# CC2530-CP2102-USB-V02-006.net
KiCad netlist of a schematic drawn in EAGLE
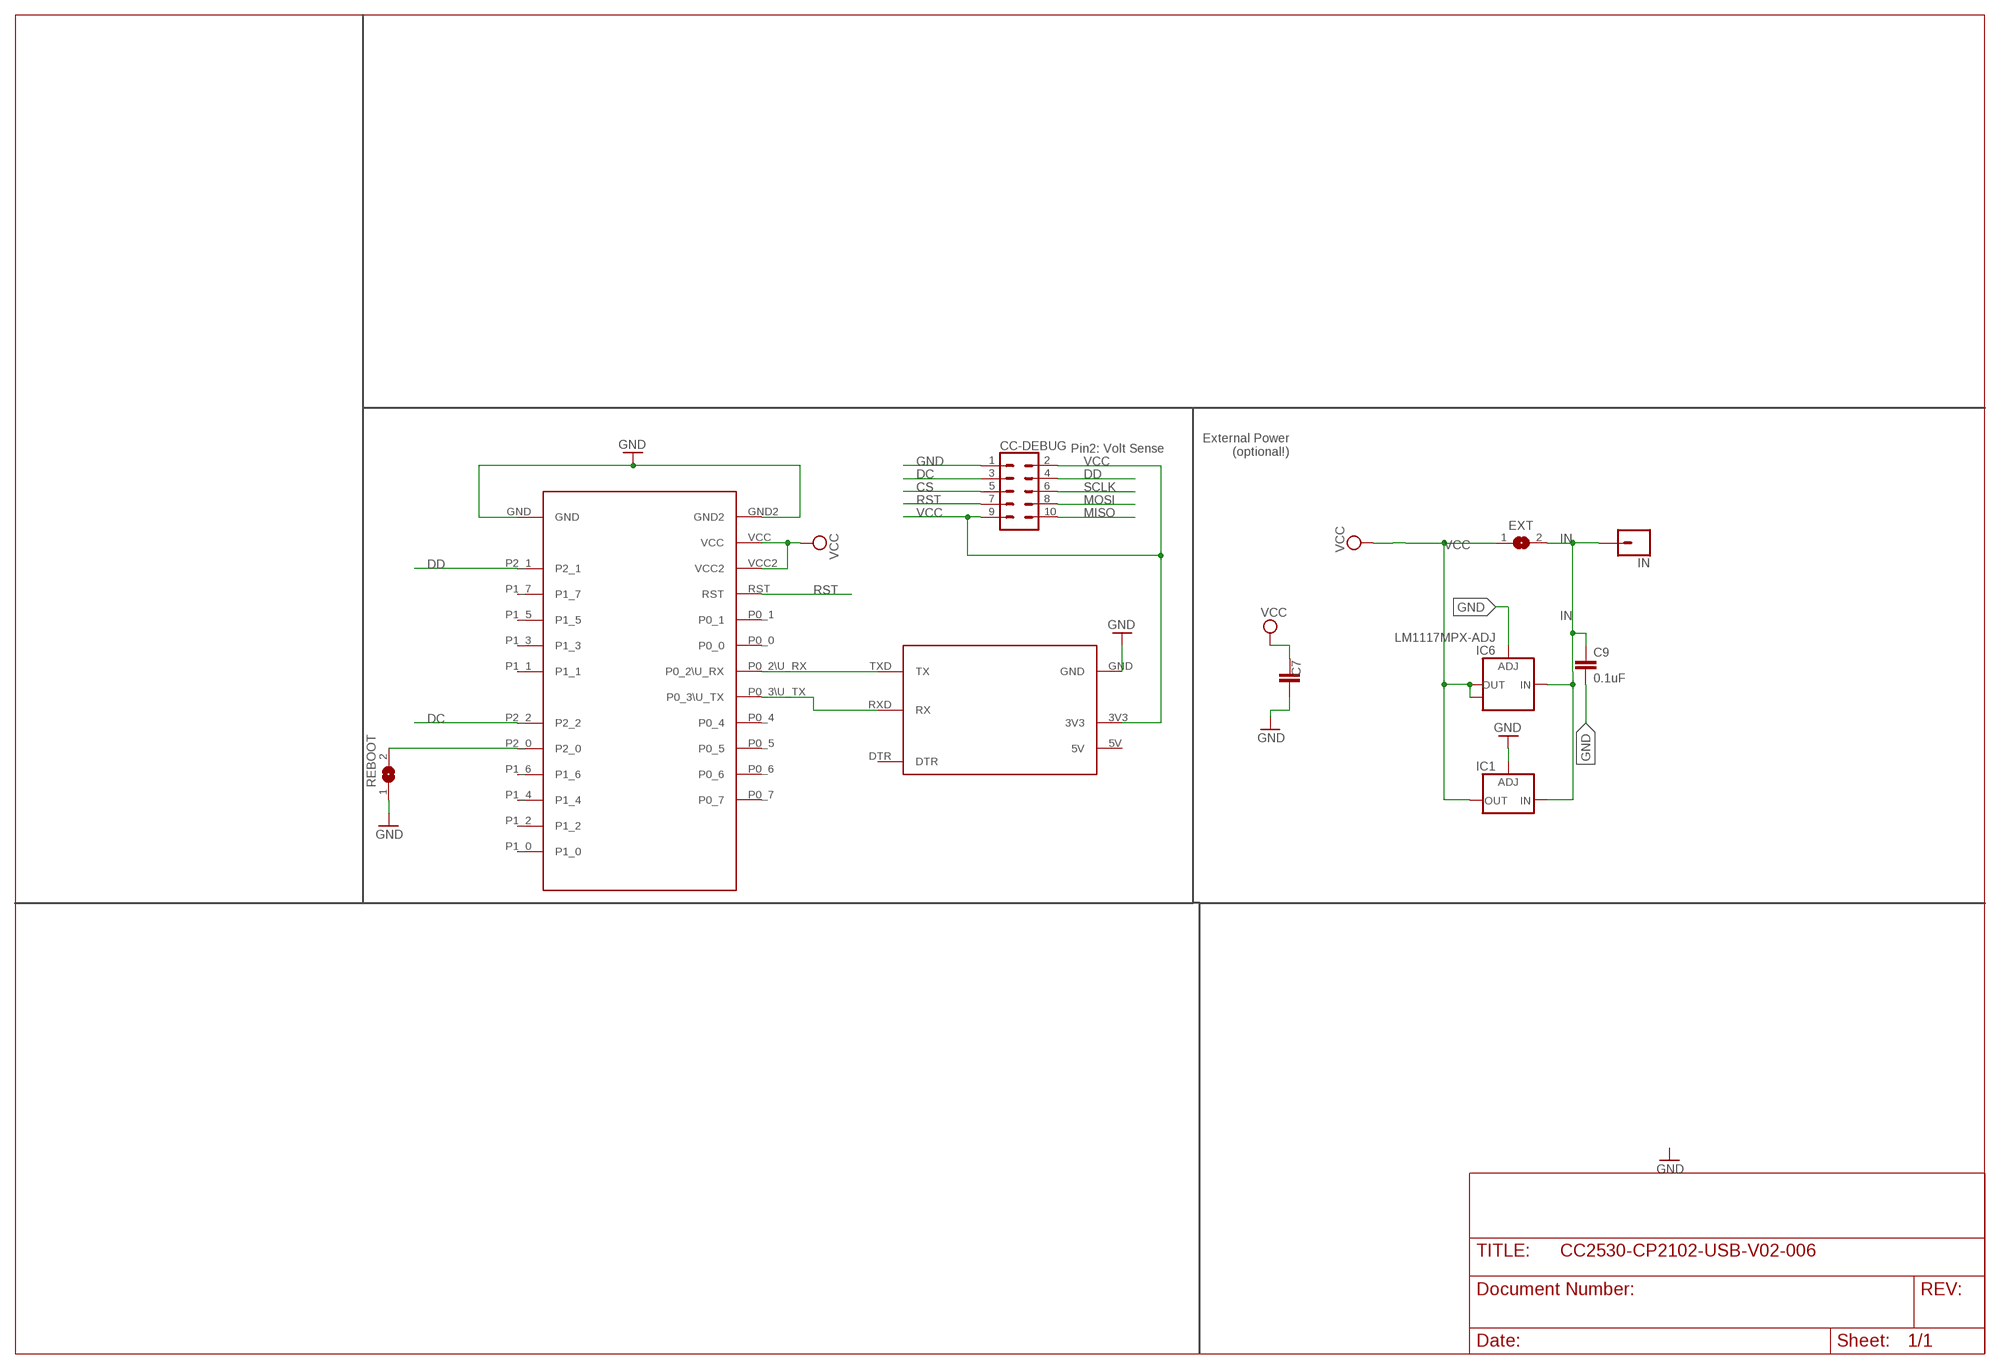
[diagram p0: schematic, sheet 1]

(export (version "E")
  (design (tool "Eeschema 10.0.6"))
  (components
    (comp (ref "C7")
      (value "C-EUC1812")
      (footprint "eagle-import:C1812")
      (libsource (lib "eagle-import") (part "C-EUC1812"))
    )
    (comp (ref "C9")
      (value "0.1uF")
      (footprint "eagle-import:C1206")
      (libsource (lib "eagle-import") (part "C-EUC1206"))
    )
    (comp (ref "CC-DEBUG")
      (value "CONN_05X2SHD_LOCK")
      (footprint "eagle-import:2X5-SHROUDED_LOCK")
      (libsource (lib "eagle-import") (part "CONN_05X2SHD_LOCK"))
    )
    (comp (ref "EXT") (value "SJ") (footprint "eagle-import:SJ") (libsource (lib "eagle-import") (part "SJ")))
    (comp (ref "IC1")
      (value "LD117ADT50TR")
      (footprint "eagle-import:DPACK")
      (libsource (lib "eagle-import") (part "LD117A?DT50TR"))
    )
    (comp (ref "IC6")
      (value "LM1117MPX-ADJ")
      (footprint "eagle-import:SOT223")
      (libsource (lib "eagle-import") (part "LM1117MPX-ADJ"))
    )
    (comp (ref "IN")
      (value "CONN_01")
      (footprint "eagle-import:1X01")
      (libsource (lib "eagle-import") (part "CONN_01"))
    )
    (comp (ref "REBOOT")
      (value "SJ")
      (footprint "eagle-import:SJ")
      (libsource (lib "eagle-import") (part "SJ"))
    )
    (comp (ref "U$1")
      (value "CP2101")
      (footprint "eagle-import:CP2101-BEAKOUT")
      (libsource (lib "eagle-import") (part "CP2101"))
    )
    (comp (ref "U$3")
      (value "CC2530_MODULE")
      (footprint "eagle-import:CC2530_DIL")
      (libsource (lib "eagle-import") (part "CC2530_MODULE"))
    )
  )
  (nets
    (net (code "1") (name "/5V") (class "Default")
      (node (ref "U$1") (pin "5V") (pinfunction "5V_5V") (pintype "power_in"))
    )
    (net (code "2") (name "/CS") (class "Default")
      (node (ref "CC-DEBUG") (pin "5") (pinfunction "5_5") (pintype "passive"))
    )
    (net (code "3") (name "/DC") (class "Default")
      (node (ref "CC-DEBUG") (pin "3") (pinfunction "3_3") (pintype "passive"))
      (node (ref "U$3") (pin "P2_2") (pinfunction "P2_2_P2_2") (pintype "bidirectional"))
    )
    (net (code "4") (name "/DD") (class "Default")
      (node (ref "CC-DEBUG") (pin "4") (pinfunction "4_4") (pintype "passive"))
      (node (ref "U$3") (pin "P2_1") (pinfunction "P2_1_P2_1") (pintype "bidirectional"))
    )
    (net (code "5") (name "/IN") (class "Default")
      (node (ref "C9") (pin "1") (pinfunction "1_1") (pintype "passive"))
      (node (ref "EXT") (pin "2") (pinfunction "2_2") (pintype "passive"))
      (node (ref "IC1") (pin "3") (pinfunction "IN_3") (pintype "input"))
      (node (ref "IC6") (pin "3") (pinfunction "IN_3") (pintype "input"))
      (node (ref "IN") (pin "1") (pinfunction "1_1") (pintype "passive"))
    )
    (net (code "6") (name "/MISO") (class "Default")
      (node (ref "CC-DEBUG") (pin "10") (pinfunction "10_10") (pintype "passive"))
    )
    (net (code "7") (name "/MOSI") (class "Default")
      (node (ref "CC-DEBUG") (pin "8") (pinfunction "8_8") (pintype "passive"))
    )
    (net (code "8") (name "/RST") (class "Default")
      (node (ref "CC-DEBUG") (pin "7") (pinfunction "7_7") (pintype "passive"))
      (node (ref "U$3") (pin "RST") (pinfunction "RST_RST") (pintype "bidirectional"))
    )
    (net (code "9") (name "/SCLK") (class "Default")
      (node (ref "CC-DEBUG") (pin "6") (pinfunction "6_6") (pintype "passive"))
    )
    (net (code "10") (name "GND") (class "Default")
      (node (ref "C7") (pin "1") (pinfunction "1_1") (pintype "passive"))
      (node (ref "C9") (pin "2") (pinfunction "2_2") (pintype "passive"))
      (node (ref "CC-DEBUG") (pin "1") (pinfunction "1_1") (pintype "passive"))
      (node (ref "IC1") (pin "1") (pinfunction "ADJ_1") (pintype "input"))
      (node (ref "IC6") (pin "1") (pinfunction "ADJ_1") (pintype "input"))
      (node (ref "REBOOT") (pin "1") (pinfunction "1_1") (pintype "passive"))
      (node (ref "U$1") (pin "GND") (pinfunction "GND_GND") (pintype "power_in"))
      (node (ref "U$3") (pin "GND") (pinfunction "GND_GND") (pintype "bidirectional"))
      (node (ref "U$3") (pin "GND2") (pinfunction "GND2_GND2") (pintype "bidirectional"))
    )
    (net (code "11") (name "Net-(REBOOT-Pad2)") (class "Default")
      (node (ref "REBOOT") (pin "2") (pinfunction "2_2") (pintype "passive"))
      (node (ref "U$3") (pin "P2_0") (pinfunction "P2_0_P2_0") (pintype "bidirectional"))
    )
    (net (code "12") (name "Net-(U$1-RX)") (class "Default")
      (node (ref "U$1") (pin "RXD") (pinfunction "RX_RXD") (pintype "input"))
      (node (ref "U$3") (pin "P0_3\\U_TX") (pinfunction "P0_3\\U_TX_P0_3\\U_TX") (pintype "bidirectional"))
    )
    (net (code "13") (name "Net-(U$1-TX)") (class "Default")
      (node (ref "U$1") (pin "TXD") (pinfunction "TX_TXD") (pintype "output"))
      (node (ref "U$3") (pin "P0_2\\U_RX") (pinfunction "P0_2\\U_RX_P0_2\\U_RX") (pintype "bidirectional"))
    )
    (net (code "14") (name "VCC") (class "Default")
      (node (ref "C7") (pin "2") (pinfunction "2_2") (pintype "passive"))
      (node (ref "CC-DEBUG") (pin "2") (pinfunction "2_2") (pintype "passive"))
      (node (ref "CC-DEBUG") (pin "9") (pinfunction "9_9") (pintype "passive"))
      (node (ref "EXT") (pin "1") (pinfunction "1_1") (pintype "passive"))
      (node (ref "IC1") (pin "4") (pinfunction "OUT_4") (pintype "passive"))
      (node (ref "IC6") (pin "2") (pinfunction "OUT_2") (pintype "passive"))
      (node (ref "IC6") (pin "TAB") (pinfunction "OUT1_TAB") (pintype "passive"))
      (node (ref "U$1") (pin "3V3") (pinfunction "3V3_3V3") (pintype "power_in"))
      (node (ref "U$3") (pin "VCC") (pinfunction "VCC_VCC") (pintype "bidirectional"))
      (node (ref "U$3") (pin "VCC2") (pinfunction "VCC2_VCC2") (pintype "bidirectional"))
    )
    (net (code "15") (name "unconnected-(U$1-PadDTR)") (class "Default")
      (node (ref "U$1") (pin "DTR") (pinfunction "DTR_DTR") (pintype "bidirectional"))
    )
    (net (code "16") (name "unconnected-(U$3-PadP0_0)") (class "Default")
      (node (ref "U$3") (pin "P0_0") (pinfunction "P0_0_P0_0") (pintype "bidirectional"))
    )
    (net (code "17") (name "unconnected-(U$3-PadP0_1)") (class "Default")
      (node (ref "U$3") (pin "P0_1") (pinfunction "P0_1_P0_1") (pintype "bidirectional"))
    )
    (net (code "18") (name "unconnected-(U$3-PadP0_4)") (class "Default")
      (node (ref "U$3") (pin "P0_4") (pinfunction "P0_4_P0_4") (pintype "bidirectional"))
    )
    (net (code "19") (name "unconnected-(U$3-PadP0_5)") (class "Default")
      (node (ref "U$3") (pin "P0_5") (pinfunction "P0_5_P0_5") (pintype "bidirectional"))
    )
    (net (code "20") (name "unconnected-(U$3-PadP0_6)") (class "Default")
      (node (ref "U$3") (pin "P0_6") (pinfunction "P0_6_P0_6") (pintype "bidirectional"))
    )
    (net (code "21") (name "unconnected-(U$3-PadP0_7)") (class "Default")
      (node (ref "U$3") (pin "P0_7") (pinfunction "P0_7_P0_7") (pintype "bidirectional"))
    )
    (net (code "22") (name "unconnected-(U$3-PadP1_0)") (class "Default")
      (node (ref "U$3") (pin "P1_0") (pinfunction "P1_0_P1_0") (pintype "bidirectional"))
    )
    (net (code "23") (name "unconnected-(U$3-PadP1_1)") (class "Default")
      (node (ref "U$3") (pin "P1_1") (pinfunction "P1_1_P1_1") (pintype "bidirectional"))
    )
    (net (code "24") (name "unconnected-(U$3-PadP1_2)") (class "Default")
      (node (ref "U$3") (pin "P1_2") (pinfunction "P1_2_P1_2") (pintype "bidirectional"))
    )
    (net (code "25") (name "unconnected-(U$3-PadP1_3)") (class "Default")
      (node (ref "U$3") (pin "P1_3") (pinfunction "P1_3_P1_3") (pintype "bidirectional"))
    )
    (net (code "26") (name "unconnected-(U$3-PadP1_4)") (class "Default")
      (node (ref "U$3") (pin "P1_4") (pinfunction "P1_4_P1_4") (pintype "bidirectional"))
    )
    (net (code "27") (name "unconnected-(U$3-PadP1_5)") (class "Default")
      (node (ref "U$3") (pin "P1_5") (pinfunction "P1_5_P1_5") (pintype "bidirectional"))
    )
    (net (code "28") (name "unconnected-(U$3-PadP1_6)") (class "Default")
      (node (ref "U$3") (pin "P1_6") (pinfunction "P1_6_P1_6") (pintype "bidirectional"))
    )
    (net (code "29") (name "unconnected-(U$3-PadP1_7)") (class "Default")
      (node (ref "U$3") (pin "P1_7") (pinfunction "P1_7_P1_7") (pintype "bidirectional"))
    )
  )
)
